# Interface_CLPToDigital.net
KiCad netlist of a schematic drawn in Altium Designer
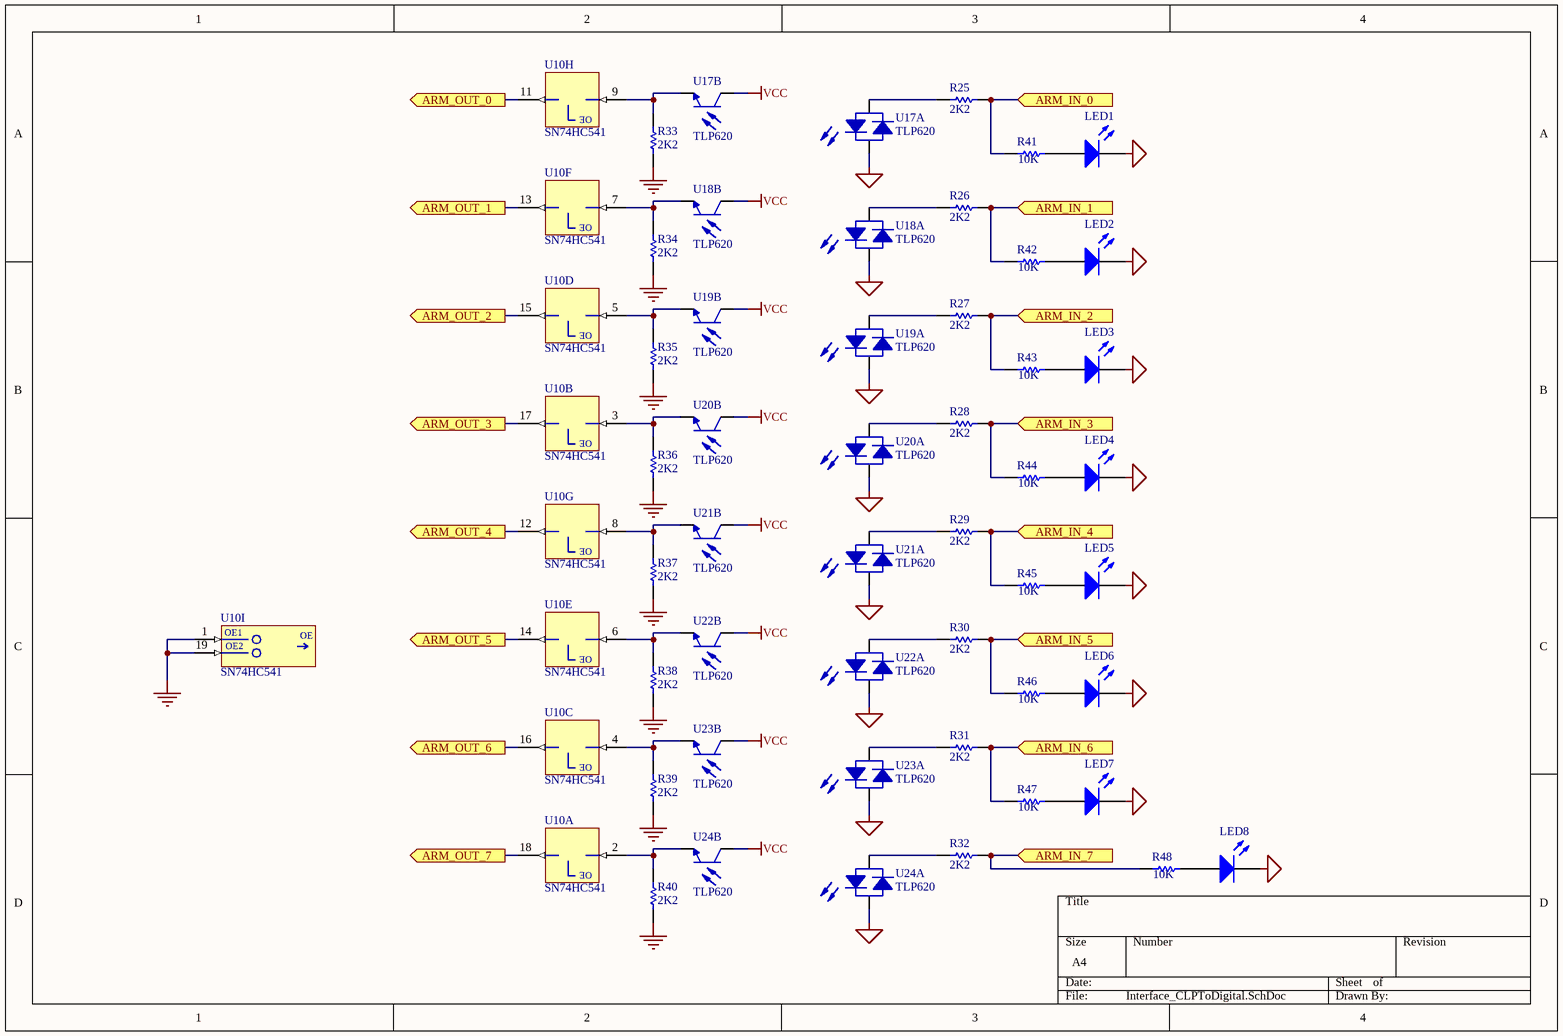
[diagram p0: Interface_CLPToDigital.SchDoc]

(export (version "E")
  (design (tool "Eeschema 10.0.6"))
  (components
    (comp (ref "LED1")
      (value "151053YS04500")
      (footprint "Type 5mm")
      (description "THT LED round mono-color waterclear, WL-TMRW, Yellow")
      (fields (field (name "MANUFACTURER") "Wuerth Elektronik"))
      (libsource (lib "Altium Content Vault") (part "WE-LED_K1A2-2"))
    )
    (comp (ref "LED2")
      (value "151053YS04500")
      (footprint "Type 5mm")
      (description "THT LED round mono-color waterclear, WL-TMRW, Yellow")
      (fields (field (name "MANUFACTURER") "Wuerth Elektronik"))
      (libsource (lib "Altium Content Vault") (part "WE-LED_K1A2-2"))
    )
    (comp (ref "LED3")
      (value "151053YS04500")
      (footprint "Type 5mm")
      (description "THT LED round mono-color waterclear, WL-TMRW, Yellow")
      (fields (field (name "MANUFACTURER") "Wuerth Elektronik"))
      (libsource (lib "Altium Content Vault") (part "WE-LED_K1A2-2"))
    )
    (comp (ref "LED4")
      (value "151053YS04500")
      (footprint "Type 5mm")
      (description "THT LED round mono-color waterclear, WL-TMRW, Yellow")
      (fields (field (name "MANUFACTURER") "Wuerth Elektronik"))
      (libsource (lib "Altium Content Vault") (part "WE-LED_K1A2-2"))
    )
    (comp (ref "LED5")
      (value "151053YS04500")
      (footprint "Type 5mm")
      (description "THT LED round mono-color waterclear, WL-TMRW, Yellow")
      (fields (field (name "MANUFACTURER") "Wuerth Elektronik"))
      (libsource (lib "Altium Content Vault") (part "WE-LED_K1A2-2"))
    )
    (comp (ref "LED6")
      (value "151053YS04500")
      (footprint "Type 5mm")
      (description "THT LED round mono-color waterclear, WL-TMRW, Yellow")
      (fields (field (name "MANUFACTURER") "Wuerth Elektronik"))
      (libsource (lib "Altium Content Vault") (part "WE-LED_K1A2-2"))
    )
    (comp (ref "LED7")
      (value "151053YS04500")
      (footprint "Type 5mm")
      (description "THT LED round mono-color waterclear, WL-TMRW, Yellow")
      (fields (field (name "MANUFACTURER") "Wuerth Elektronik"))
      (libsource (lib "Altium Content Vault") (part "WE-LED_K1A2-2"))
    )
    (comp (ref "LED8")
      (value "151053YS04500")
      (footprint "Type 5mm")
      (description "THT LED round mono-color waterclear, WL-TMRW, Yellow")
      (fields (field (name "MANUFACTURER") "Wuerth Elektronik"))
      (libsource (lib "Altium Content Vault") (part "WE-LED_K1A2-2"))
    )
    (comp (ref "R25")
      (value "2K2")
      (footprint "CR25")
      (description "Resistor")
      (libsource (lib "Basic") (part "Resistor"))
    )
    (comp (ref "R26")
      (value "2K2")
      (footprint "CR25")
      (description "Resistor")
      (libsource (lib "Basic") (part "Resistor"))
    )
    (comp (ref "R27")
      (value "2K2")
      (footprint "CR25")
      (description "Resistor")
      (libsource (lib "Basic") (part "Resistor"))
    )
    (comp (ref "R28")
      (value "2K2")
      (footprint "CR25")
      (description "Resistor")
      (libsource (lib "Basic") (part "Resistor"))
    )
    (comp (ref "R29")
      (value "2K2")
      (footprint "CR25")
      (description "Resistor")
      (libsource (lib "Basic") (part "Resistor"))
    )
    (comp (ref "R30")
      (value "2K2")
      (footprint "CR25")
      (description "Resistor")
      (libsource (lib "Basic") (part "Resistor"))
    )
    (comp (ref "R31")
      (value "2K2")
      (footprint "CR25")
      (description "Resistor")
      (libsource (lib "Basic") (part "Resistor"))
    )
    (comp (ref "R32")
      (value "2K2")
      (footprint "CR25")
      (description "Resistor")
      (libsource (lib "Basic") (part "Resistor"))
    )
    (comp (ref "R33")
      (value "2K2")
      (footprint "CR25")
      (description "Resistor")
      (libsource (lib "Basic") (part "Resistor"))
    )
    (comp (ref "R34")
      (value "2K2")
      (footprint "CR25")
      (description "Resistor")
      (libsource (lib "Basic") (part "Resistor"))
    )
    (comp (ref "R35")
      (value "2K2")
      (footprint "CR25")
      (description "Resistor")
      (libsource (lib "Basic") (part "Resistor"))
    )
    (comp (ref "R36")
      (value "2K2")
      (footprint "CR25")
      (description "Resistor")
      (libsource (lib "Basic") (part "Resistor"))
    )
    (comp (ref "R37")
      (value "2K2")
      (footprint "CR25")
      (description "Resistor")
      (libsource (lib "Basic") (part "Resistor"))
    )
    (comp (ref "R38")
      (value "2K2")
      (footprint "CR25")
      (description "Resistor")
      (libsource (lib "Basic") (part "Resistor"))
    )
    (comp (ref "R39")
      (value "2K2")
      (footprint "CR25")
      (description "Resistor")
      (libsource (lib "Basic") (part "Resistor"))
    )
    (comp (ref "R40")
      (value "2K2")
      (footprint "CR25")
      (description "Resistor")
      (libsource (lib "Basic") (part "Resistor"))
    )
    (comp (ref "R41")
      (value "10K")
      (footprint "AXIAL-0.5")
      (description "Resistor")
      (fields (field (name "Comment") "1") (field (name "PUBLISHER") "Altium Limited"))
      (libsource (lib "Miscellaneous Devices") (part "Res1"))
    )
    (comp (ref "R42")
      (value "10K")
      (footprint "AXIAL-0.5")
      (description "Resistor")
      (fields (field (name "Comment") "Res1") (field (name "PUBLISHER") "Altium Limited"))
      (libsource (lib "Miscellaneous Devices") (part "Res1"))
    )
    (comp (ref "R43")
      (value "10K")
      (footprint "AXIAL-0.5")
      (description "Resistor")
      (fields (field (name "Comment") "Res1") (field (name "PUBLISHER") "Altium Limited"))
      (libsource (lib "Miscellaneous Devices") (part "Res1"))
    )
    (comp (ref "R44")
      (value "10K")
      (footprint "AXIAL-0.5")
      (description "Resistor")
      (fields (field (name "Comment") "Res1") (field (name "PUBLISHER") "Altium Limited"))
      (libsource (lib "Miscellaneous Devices") (part "Res1"))
    )
    (comp (ref "R45")
      (value "10K")
      (footprint "AXIAL-0.5")
      (description "Resistor")
      (fields (field (name "Comment") "Res1") (field (name "PUBLISHER") "Altium Limited"))
      (libsource (lib "Miscellaneous Devices") (part "Res1"))
    )
    (comp (ref "R46")
      (value "10K")
      (footprint "AXIAL-0.5")
      (description "Resistor")
      (fields (field (name "Comment") "Res1") (field (name "PUBLISHER") "Altium Limited"))
      (libsource (lib "Miscellaneous Devices") (part "Res1"))
    )
    (comp (ref "R47")
      (value "10K")
      (footprint "AXIAL-0.5")
      (description "Resistor")
      (fields (field (name "Comment") "Res1") (field (name "PUBLISHER") "Altium Limited"))
      (libsource (lib "Miscellaneous Devices") (part "Res1"))
    )
    (comp (ref "R48")
      (value "10K")
      (footprint "AXIAL-0.3")
      (description "Resistor")
      (fields (field (name "Comment") "Res1") (field (name "PUBLISHER") "Altium Limited"))
      (libsource (lib "Miscellaneous Devices") (part "Res1"))
    )
    (comp (ref "U10")
      (value "SN74HC541")
      (footprint "PDIP20")
      (description "Octal Buffers and Line Drivers With 3-State Outputs")
      (libsource (lib "Texas Instruments") (part "SN74HC541"))
    )
    (comp (ref "U17")
      (value "TLP620")
      (footprint "DIP4")
      (description "TOSHIBA Photocoupler")
      (libsource (lib "Toshiba") (part "TLP620"))
    )
    (comp (ref "U18")
      (value "TLP620")
      (footprint "DIP4")
      (description "TOSHIBA Photocoupler")
      (libsource (lib "Toshiba") (part "TLP620"))
    )
    (comp (ref "U19")
      (value "TLP620")
      (footprint "DIP4")
      (description "TOSHIBA Photocoupler")
      (libsource (lib "Toshiba") (part "TLP620"))
    )
    (comp (ref "U20")
      (value "TLP620")
      (footprint "DIP4")
      (description "TOSHIBA Photocoupler")
      (libsource (lib "Toshiba") (part "TLP620"))
    )
    (comp (ref "U21")
      (value "TLP620")
      (footprint "DIP4")
      (description "TOSHIBA Photocoupler")
      (libsource (lib "Toshiba") (part "TLP620"))
    )
    (comp (ref "U22")
      (value "TLP620")
      (footprint "DIP4")
      (description "TOSHIBA Photocoupler")
      (libsource (lib "Toshiba") (part "TLP620"))
    )
    (comp (ref "U23")
      (value "TLP620")
      (footprint "DIP4")
      (description "TOSHIBA Photocoupler")
      (libsource (lib "Toshiba") (part "TLP620"))
    )
    (comp (ref "U24")
      (value "TLP620")
      (footprint "DIP4")
      (description "TOSHIBA Photocoupler")
      (libsource (lib "Toshiba") (part "TLP620"))
    )
  )
  (nets
    (net (code "1") (name "/ARM_IN_0") (class "Default")
      (node (ref "R25") (pin "2") (pinfunction "2_2") (pintype "passive"))
      (node (ref "R41") (pin "2") (pinfunction "2_2") (pintype "passive"))
    )
    (net (code "2") (name "/ARM_IN_1") (class "Default")
      (node (ref "R26") (pin "2") (pinfunction "2_2") (pintype "passive"))
      (node (ref "R42") (pin "2") (pinfunction "2_2") (pintype "passive"))
    )
    (net (code "3") (name "/ARM_IN_2") (class "Default")
      (node (ref "R27") (pin "2") (pinfunction "2_2") (pintype "passive"))
      (node (ref "R43") (pin "2") (pinfunction "2_2") (pintype "passive"))
    )
    (net (code "4") (name "/ARM_IN_3") (class "Default")
      (node (ref "R28") (pin "2") (pinfunction "2_2") (pintype "passive"))
      (node (ref "R44") (pin "2") (pinfunction "2_2") (pintype "passive"))
    )
    (net (code "5") (name "/ARM_IN_4") (class "Default")
      (node (ref "R29") (pin "2") (pinfunction "2_2") (pintype "passive"))
      (node (ref "R45") (pin "2") (pinfunction "2_2") (pintype "passive"))
    )
    (net (code "6") (name "/ARM_IN_5") (class "Default")
      (node (ref "R30") (pin "2") (pinfunction "2_2") (pintype "passive"))
      (node (ref "R46") (pin "2") (pinfunction "2_2") (pintype "passive"))
    )
    (net (code "7") (name "/ARM_IN_6") (class "Default")
      (node (ref "R31") (pin "2") (pinfunction "2_2") (pintype "passive"))
      (node (ref "R47") (pin "2") (pinfunction "2_2") (pintype "passive"))
    )
    (net (code "8") (name "/ARM_IN_7") (class "Default")
      (node (ref "R32") (pin "2") (pinfunction "2_2") (pintype "passive"))
      (node (ref "R48") (pin "2") (pinfunction "2_2") (pintype "passive"))
    )
    (net (code "9") (name "/ARM_OUT_0") (class "Default")
      (node (ref "U10") (pin "11") (pinfunction "Y8_11") (pintype "output"))
    )
    (net (code "10") (name "/ARM_OUT_1") (class "Default")
      (node (ref "U10") (pin "13") (pinfunction "Y6_13") (pintype "output"))
    )
    (net (code "11") (name "/ARM_OUT_2") (class "Default")
      (node (ref "U10") (pin "15") (pinfunction "Y4_15") (pintype "output"))
    )
    (net (code "12") (name "/ARM_OUT_3") (class "Default")
      (node (ref "U10") (pin "17") (pinfunction "Y2_17") (pintype "output"))
    )
    (net (code "13") (name "/ARM_OUT_4") (class "Default")
      (node (ref "U10") (pin "12") (pinfunction "Y7_12") (pintype "output"))
    )
    (net (code "14") (name "/ARM_OUT_5") (class "Default")
      (node (ref "U10") (pin "14") (pinfunction "Y5_14") (pintype "output"))
    )
    (net (code "15") (name "/ARM_OUT_6") (class "Default")
      (node (ref "U10") (pin "16") (pinfunction "Y3_16") (pintype "output"))
    )
    (net (code "16") (name "/ARM_OUT_7") (class "Default")
      (node (ref "U10") (pin "18") (pinfunction "Y1_18") (pintype "output"))
    )
    (net (code "17") (name "CLP_GND") (class "Default")
      (node (ref "LED1") (pin "1") (pinfunction "K_1") (pintype "passive"))
      (node (ref "LED2") (pin "1") (pinfunction "K_1") (pintype "passive"))
      (node (ref "LED3") (pin "1") (pinfunction "K_1") (pintype "passive"))
      (node (ref "LED4") (pin "1") (pinfunction "K_1") (pintype "passive"))
      (node (ref "LED5") (pin "1") (pinfunction "K_1") (pintype "passive"))
      (node (ref "LED6") (pin "1") (pinfunction "K_1") (pintype "passive"))
      (node (ref "LED7") (pin "1") (pinfunction "K_1") (pintype "passive"))
      (node (ref "LED8") (pin "1") (pinfunction "K_1") (pintype "passive"))
      (node (ref "U17") (pin "2") (pinfunction "2_2") (pintype "passive"))
      (node (ref "U18") (pin "2") (pinfunction "2_2") (pintype "passive"))
      (node (ref "U19") (pin "2") (pinfunction "2_2") (pintype "passive"))
      (node (ref "U20") (pin "2") (pinfunction "2_2") (pintype "passive"))
      (node (ref "U21") (pin "2") (pinfunction "2_2") (pintype "passive"))
      (node (ref "U22") (pin "2") (pinfunction "2_2") (pintype "passive"))
      (node (ref "U23") (pin "2") (pinfunction "2_2") (pintype "passive"))
      (node (ref "U24") (pin "2") (pinfunction "2_2") (pintype "passive"))
    )
    (net (code "18") (name "GND") (class "Default")
      (node (ref "R33") (pin "1") (pinfunction "1_1") (pintype "passive"))
      (node (ref "R34") (pin "1") (pinfunction "1_1") (pintype "passive"))
      (node (ref "R35") (pin "2") (pinfunction "2_2") (pintype "passive"))
      (node (ref "R36") (pin "1") (pinfunction "1_1") (pintype "passive"))
      (node (ref "R37") (pin "1") (pinfunction "1_1") (pintype "passive"))
      (node (ref "R38") (pin "1") (pinfunction "1_1") (pintype "passive"))
      (node (ref "R39") (pin "1") (pinfunction "1_1") (pintype "passive"))
      (node (ref "R40") (pin "1") (pinfunction "1_1") (pintype "passive"))
      (node (ref "U10") (pin "1") (pinfunction "OE1_1") (pintype "input"))
      (node (ref "U10") (pin "19") (pinfunction "OE2_19") (pintype "input"))
    )
    (net (code "19") (name "Net-(LED1-A)") (class "Default")
      (node (ref "LED1") (pin "2") (pinfunction "A_2") (pintype "passive"))
      (node (ref "R41") (pin "1") (pinfunction "1_1") (pintype "passive"))
    )
    (net (code "20") (name "Net-(LED2-A)") (class "Default")
      (node (ref "LED2") (pin "2") (pinfunction "A_2") (pintype "passive"))
      (node (ref "R42") (pin "1") (pinfunction "1_1") (pintype "passive"))
    )
    (net (code "21") (name "Net-(LED3-A)") (class "Default")
      (node (ref "LED3") (pin "2") (pinfunction "A_2") (pintype "passive"))
      (node (ref "R43") (pin "1") (pinfunction "1_1") (pintype "passive"))
    )
    (net (code "22") (name "Net-(LED4-A)") (class "Default")
      (node (ref "LED4") (pin "2") (pinfunction "A_2") (pintype "passive"))
      (node (ref "R44") (pin "1") (pinfunction "1_1") (pintype "passive"))
    )
    (net (code "23") (name "Net-(LED5-A)") (class "Default")
      (node (ref "LED5") (pin "2") (pinfunction "A_2") (pintype "passive"))
      (node (ref "R45") (pin "1") (pinfunction "1_1") (pintype "passive"))
    )
    (net (code "24") (name "Net-(LED6-A)") (class "Default")
      (node (ref "LED6") (pin "2") (pinfunction "A_2") (pintype "passive"))
      (node (ref "R46") (pin "1") (pinfunction "1_1") (pintype "passive"))
    )
    (net (code "25") (name "Net-(LED7-A)") (class "Default")
      (node (ref "LED7") (pin "2") (pinfunction "A_2") (pintype "passive"))
      (node (ref "R47") (pin "1") (pinfunction "1_1") (pintype "passive"))
    )
    (net (code "26") (name "Net-(LED8-A)") (class "Default")
      (node (ref "LED8") (pin "2") (pinfunction "A_2") (pintype "passive"))
      (node (ref "R48") (pin "1") (pinfunction "1_1") (pintype "passive"))
    )
    (net (code "27") (name "Net-(R25-Pad1)") (class "Default")
      (node (ref "R25") (pin "1") (pinfunction "1_1") (pintype "passive"))
      (node (ref "U17") (pin "1") (pinfunction "1_1") (pintype "passive"))
    )
    (net (code "28") (name "Net-(R26-Pad1)") (class "Default")
      (node (ref "R26") (pin "1") (pinfunction "1_1") (pintype "passive"))
      (node (ref "U18") (pin "1") (pinfunction "1_1") (pintype "passive"))
    )
    (net (code "29") (name "Net-(R27-Pad1)") (class "Default")
      (node (ref "R27") (pin "1") (pinfunction "1_1") (pintype "passive"))
      (node (ref "U19") (pin "1") (pinfunction "1_1") (pintype "passive"))
    )
    (net (code "30") (name "Net-(R28-Pad1)") (class "Default")
      (node (ref "R28") (pin "1") (pinfunction "1_1") (pintype "passive"))
      (node (ref "U20") (pin "1") (pinfunction "1_1") (pintype "passive"))
    )
    (net (code "31") (name "Net-(R29-Pad1)") (class "Default")
      (node (ref "R29") (pin "1") (pinfunction "1_1") (pintype "passive"))
      (node (ref "U21") (pin "1") (pinfunction "1_1") (pintype "passive"))
    )
    (net (code "32") (name "Net-(R30-Pad1)") (class "Default")
      (node (ref "R30") (pin "1") (pinfunction "1_1") (pintype "passive"))
      (node (ref "U22") (pin "1") (pinfunction "1_1") (pintype "passive"))
    )
    (net (code "33") (name "Net-(R31-Pad1)") (class "Default")
      (node (ref "R31") (pin "1") (pinfunction "1_1") (pintype "passive"))
      (node (ref "U23") (pin "1") (pinfunction "1_1") (pintype "passive"))
    )
    (net (code "34") (name "Net-(R32-Pad1)") (class "Default")
      (node (ref "R32") (pin "1") (pinfunction "1_1") (pintype "passive"))
      (node (ref "U24") (pin "1") (pinfunction "1_1") (pintype "passive"))
    )
    (net (code "35") (name "Net-(U10A-A1)") (class "Default")
      (node (ref "R40") (pin "2") (pinfunction "2_2") (pintype "passive"))
      (node (ref "U10") (pin "2") (pinfunction "A1_2") (pintype "input"))
      (node (ref "U24") (pin "3") (pinfunction "3_3") (pintype "passive"))
    )
    (net (code "36") (name "Net-(U10B-A2)") (class "Default")
      (node (ref "R36") (pin "2") (pinfunction "2_2") (pintype "passive"))
      (node (ref "U10") (pin "3") (pinfunction "A2_3") (pintype "input"))
      (node (ref "U20") (pin "3") (pinfunction "3_3") (pintype "passive"))
    )
    (net (code "37") (name "Net-(U10C-A3)") (class "Default")
      (node (ref "R39") (pin "2") (pinfunction "2_2") (pintype "passive"))
      (node (ref "U10") (pin "4") (pinfunction "A3_4") (pintype "input"))
      (node (ref "U23") (pin "3") (pinfunction "3_3") (pintype "passive"))
    )
    (net (code "38") (name "Net-(U10D-A4)") (class "Default")
      (node (ref "R35") (pin "1") (pinfunction "1_1") (pintype "passive"))
      (node (ref "U10") (pin "5") (pinfunction "A4_5") (pintype "input"))
      (node (ref "U19") (pin "3") (pinfunction "3_3") (pintype "passive"))
    )
    (net (code "39") (name "Net-(U10E-A5)") (class "Default")
      (node (ref "R38") (pin "2") (pinfunction "2_2") (pintype "passive"))
      (node (ref "U10") (pin "6") (pinfunction "A5_6") (pintype "input"))
      (node (ref "U22") (pin "3") (pinfunction "3_3") (pintype "passive"))
    )
    (net (code "40") (name "Net-(U10F-A6)") (class "Default")
      (node (ref "R34") (pin "2") (pinfunction "2_2") (pintype "passive"))
      (node (ref "U10") (pin "7") (pinfunction "A6_7") (pintype "input"))
      (node (ref "U18") (pin "3") (pinfunction "3_3") (pintype "passive"))
    )
    (net (code "41") (name "Net-(U10G-A7)") (class "Default")
      (node (ref "R37") (pin "2") (pinfunction "2_2") (pintype "passive"))
      (node (ref "U10") (pin "8") (pinfunction "A7_8") (pintype "input"))
      (node (ref "U21") (pin "3") (pinfunction "3_3") (pintype "passive"))
    )
    (net (code "42") (name "Net-(U10H-A8)") (class "Default")
      (node (ref "R33") (pin "2") (pinfunction "2_2") (pintype "passive"))
      (node (ref "U10") (pin "9") (pinfunction "A8_9") (pintype "input"))
      (node (ref "U17") (pin "3") (pinfunction "3_3") (pintype "passive"))
    )
    (net (code "43") (name "VCC") (class "Default")
      (node (ref "U17") (pin "4") (pinfunction "4_4") (pintype "passive"))
      (node (ref "U18") (pin "4") (pinfunction "4_4") (pintype "passive"))
      (node (ref "U19") (pin "4") (pinfunction "4_4") (pintype "passive"))
      (node (ref "U20") (pin "4") (pinfunction "4_4") (pintype "passive"))
      (node (ref "U21") (pin "4") (pinfunction "4_4") (pintype "passive"))
      (node (ref "U22") (pin "4") (pinfunction "4_4") (pintype "passive"))
      (node (ref "U23") (pin "4") (pinfunction "4_4") (pintype "passive"))
      (node (ref "U24") (pin "4") (pinfunction "4_4") (pintype "passive"))
    )
  )
)
